# electronic_system.net
KiCad netlist of a schematic drawn in EAGLE
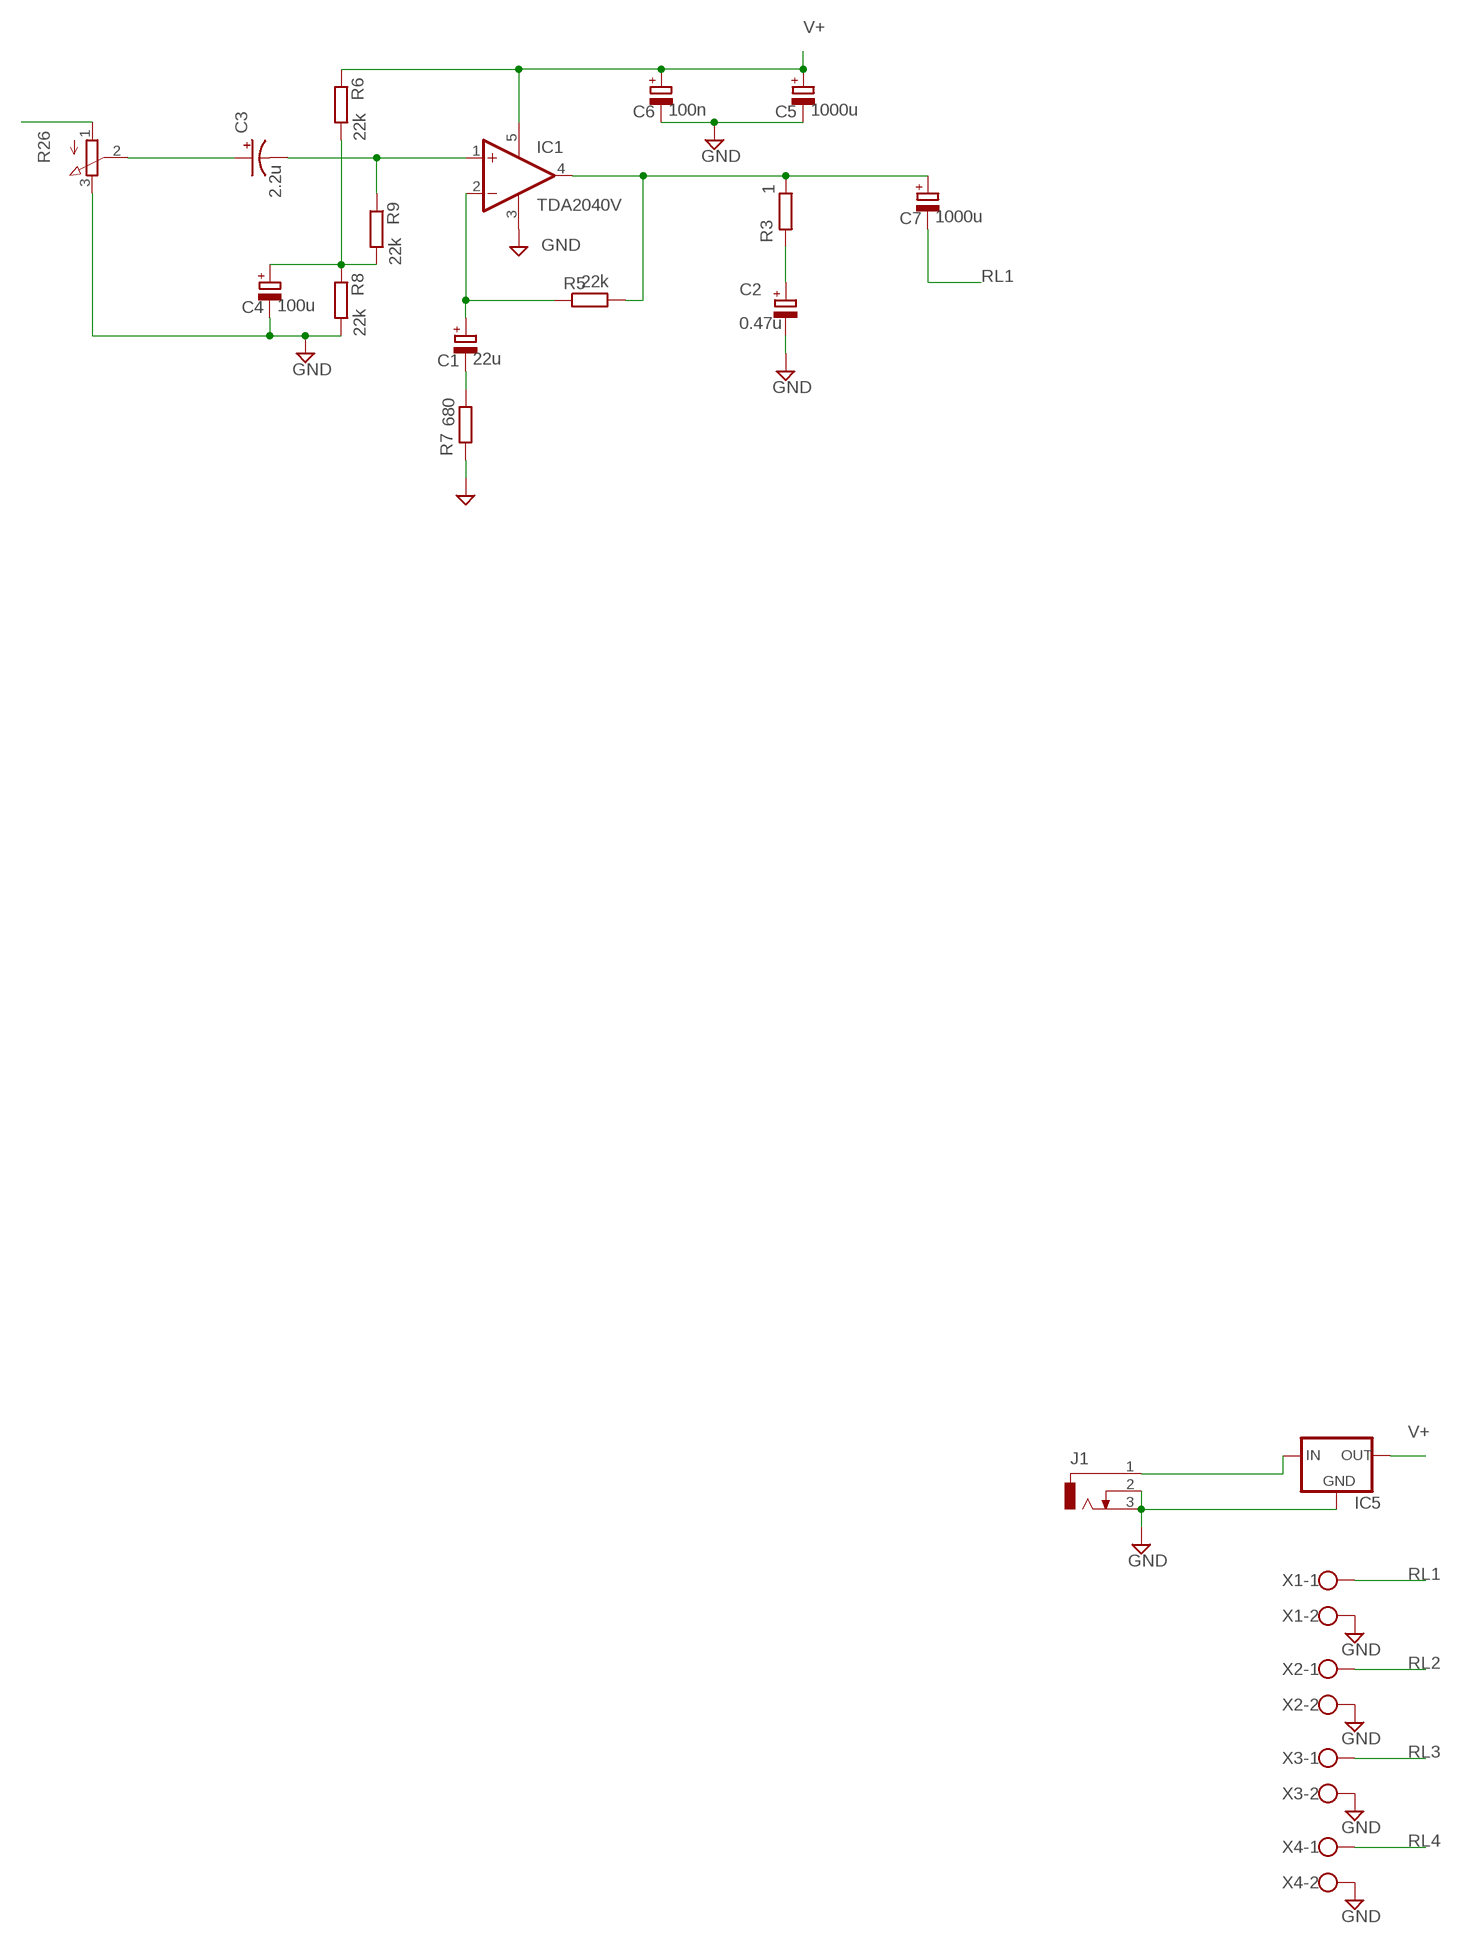
[diagram p0: schematic, sheet 1]

(export (version "E")
  (design (tool "Eeschema 10.0.6"))
  (components
    (comp (ref "C1")
      (value "22u")
      (footprint "eagle-import:E5-6")
      (libsource (lib "eagle-import") (part "CPOL-EUE5-6"))
    )
    (comp (ref "C2")
      (value "0.47u")
      (footprint "eagle-import:E5-5")
      (libsource (lib "eagle-import") (part "CPOL-EUE5-5"))
    )
    (comp (ref "C3")
      (value "2.2u")
      (footprint "eagle-import:TT5D11")
      (libsource (lib "eagle-import") (part "CPOL-USTT5D11"))
    )
    (comp (ref "C4")
      (value "100u")
      (footprint "eagle-import:E5-10,5")
      (libsource (lib "eagle-import") (part "CPOL-EUE5-10.5"))
    )
    (comp (ref "C5")
      (value "1000u")
      (footprint "eagle-import:E5-10,5")
      (libsource (lib "eagle-import") (part "CPOL-EUE5-10.5"))
    )
    (comp (ref "C6")
      (value "100n")
      (footprint "eagle-import:E5-5")
      (libsource (lib "eagle-import") (part "CPOL-EUE5-5"))
    )
    (comp (ref "C7")
      (value "1000u")
      (footprint "eagle-import:E5-10,5")
      (libsource (lib "eagle-import") (part "CPOL-EUE5-10.5"))
    )
    (comp (ref "IC1")
      (value "TDA2040V")
      (footprint "eagle-import:CB360")
      (libsource (lib "eagle-import") (part "TDA2040V"))
    )
    (comp (ref "IC5")
      (value "78XXS")
      (footprint "eagle-import:78XXS")
      (libsource (lib "eagle-import") (part "78XXS"))
    )
    (comp (ref "J1")
      (value "DCJ0303")
      (footprint "eagle-import:DCJ0303")
      (libsource (lib "eagle-import") (part "DCJ0303"))
    )
    (comp (ref "R3")
      (value "1")
      (footprint "eagle-import:0207_12")
      (libsource (lib "eagle-import") (part "R-EU_0207/12"))
    )
    (comp (ref "R5")
      (value "22k")
      (footprint "eagle-import:0207_12")
      (libsource (lib "eagle-import") (part "R-EU_0207/12"))
    )
    (comp (ref "R6")
      (value "22k")
      (footprint "eagle-import:0207_12")
      (libsource (lib "eagle-import") (part "R-EU_0207/12"))
    )
    (comp (ref "R7")
      (value "680")
      (footprint "eagle-import:0207_12")
      (libsource (lib "eagle-import") (part "R-EU_0207/12"))
    )
    (comp (ref "R8")
      (value "22k")
      (footprint "eagle-import:0207_12")
      (libsource (lib "eagle-import") (part "R-EU_0207/12"))
    )
    (comp (ref "R9")
      (value "22k")
      (footprint "eagle-import:0207_12")
      (libsource (lib "eagle-import") (part "R-EU_0207/12"))
    )
    (comp (ref "R26")
      (value "3RP/1610N")
      (footprint "eagle-import:3RP_1610N")
      (libsource (lib "eagle-import") (part "3RP/1610N"))
    )
    (comp (ref "X1")
      (value "W237-102")
      (footprint "eagle-import:W237-102")
      (fields (field (name "MPN") "237-102"))
      (libsource (lib "eagle-import") (part "W237-102"))
    )
    (comp (ref "X2")
      (value "W237-102")
      (footprint "eagle-import:W237-102")
      (fields (field (name "MPN") "237-102"))
      (libsource (lib "eagle-import") (part "W237-102"))
    )
    (comp (ref "X3")
      (value "W237-102")
      (footprint "eagle-import:W237-102")
      (fields (field (name "MPN") "237-102"))
      (libsource (lib "eagle-import") (part "W237-102"))
    )
    (comp (ref "X4")
      (value "W237-102")
      (footprint "eagle-import:W237-102")
      (fields (field (name "MPN") "237-102"))
      (libsource (lib "eagle-import") (part "W237-102"))
    )
  )
  (nets
    (net (code "1") (name "/RL1") (class "Default")
      (node (ref "C7") (pin "-") (pinfunction "-_-") (pintype "passive"))
      (node (ref "X1") (pin "1") (pinfunction "KL_1") (pintype "passive"))
    )
    (net (code "2") (name "/RL2") (class "Default")
      (node (ref "X2") (pin "1") (pinfunction "KL_1") (pintype "passive"))
    )
    (net (code "3") (name "/RL3") (class "Default")
      (node (ref "X3") (pin "1") (pinfunction "KL_1") (pintype "passive"))
    )
    (net (code "4") (name "/RL4") (class "Default")
      (node (ref "X4") (pin "1") (pinfunction "KL_1") (pintype "passive"))
    )
    (net (code "5") (name "/V+") (class "Default")
      (node (ref "C5") (pin "+") (pinfunction "+_+") (pintype "passive"))
      (node (ref "C6") (pin "+") (pinfunction "+_+") (pintype "passive"))
      (node (ref "IC1") (pin "5") (pinfunction "V+_5") (pintype "power_in"))
      (node (ref "IC5") (pin "OUT") (pinfunction "OUT_OUT") (pintype "passive"))
      (node (ref "R6") (pin "1") (pinfunction "1_1") (pintype "passive"))
    )
    (net (code "6") (name "GND") (class "Default")
      (node (ref "C2") (pin "-") (pinfunction "-_-") (pintype "passive"))
      (node (ref "C4") (pin "-") (pinfunction "-_-") (pintype "passive"))
      (node (ref "C5") (pin "-") (pinfunction "-_-") (pintype "passive"))
      (node (ref "C6") (pin "-") (pinfunction "-_-") (pintype "passive"))
      (node (ref "IC1") (pin "3") (pinfunction "V-_3") (pintype "power_in"))
      (node (ref "IC5") (pin "GND") (pinfunction "GND_GND") (pintype "input"))
      (node (ref "J1") (pin "2") (pinfunction "2_2") (pintype "passive"))
      (node (ref "J1") (pin "3") (pinfunction "3_3") (pintype "passive"))
      (node (ref "R26") (pin "3") (pinfunction "E_3") (pintype "passive"))
      (node (ref "R7") (pin "2") (pinfunction "2_2") (pintype "passive"))
      (node (ref "R8") (pin "2") (pinfunction "2_2") (pintype "passive"))
      (node (ref "X1") (pin "2") (pinfunction "KL_2") (pintype "passive"))
      (node (ref "X2") (pin "2") (pinfunction "KL_2") (pintype "passive"))
      (node (ref "X3") (pin "2") (pinfunction "KL_2") (pintype "passive"))
      (node (ref "X4") (pin "2") (pinfunction "KL_2") (pintype "passive"))
    )
    (net (code "7") (name "Net-(C1-Pad-)") (class "Default")
      (node (ref "C1") (pin "-") (pinfunction "-_-") (pintype "passive"))
      (node (ref "R7") (pin "1") (pinfunction "1_1") (pintype "passive"))
    )
    (net (code "8") (name "Net-(C2-Pad+)") (class "Default")
      (node (ref "C2") (pin "+") (pinfunction "+_+") (pintype "passive"))
      (node (ref "R3") (pin "2") (pinfunction "2_2") (pintype "passive"))
    )
    (net (code "9") (name "Net-(C4-Pad+)") (class "Default")
      (node (ref "C4") (pin "+") (pinfunction "+_+") (pintype "passive"))
      (node (ref "R6") (pin "2") (pinfunction "2_2") (pintype "passive"))
      (node (ref "R8") (pin "1") (pinfunction "1_1") (pintype "passive"))
      (node (ref "R9") (pin "2") (pinfunction "2_2") (pintype "passive"))
    )
    (net (code "10") (name "Net-(IC1-+IN)") (class "Default")
      (node (ref "C3") (pin "-") (pinfunction "-_-") (pintype "passive"))
      (node (ref "IC1") (pin "1") (pinfunction "+IN_1") (pintype "input"))
      (node (ref "R9") (pin "1") (pinfunction "1_1") (pintype "passive"))
    )
    (net (code "11") (name "Net-(IC1--IN)") (class "Default")
      (node (ref "C1") (pin "+") (pinfunction "+_+") (pintype "passive"))
      (node (ref "IC1") (pin "2") (pinfunction "-IN_2") (pintype "input"))
      (node (ref "R5") (pin "1") (pinfunction "1_1") (pintype "passive"))
    )
    (net (code "12") (name "Net-(IC1-OUT)") (class "Default")
      (node (ref "C7") (pin "+") (pinfunction "+_+") (pintype "passive"))
      (node (ref "IC1") (pin "4") (pinfunction "OUT_4") (pintype "output"))
      (node (ref "R3") (pin "1") (pinfunction "1_1") (pintype "passive"))
      (node (ref "R5") (pin "2") (pinfunction "2_2") (pintype "passive"))
    )
    (net (code "13") (name "Net-(IC5-PadIN)") (class "Default")
      (node (ref "IC5") (pin "IN") (pinfunction "IN_IN") (pintype "input"))
      (node (ref "J1") (pin "1") (pinfunction "1_1") (pintype "passive"))
    )
    (net (code "14") (name "Net-(R26-S)") (class "Default")
      (node (ref "C3") (pin "+") (pinfunction "+_+") (pintype "passive"))
      (node (ref "R26") (pin "2") (pinfunction "S_2") (pintype "passive"))
    )
    (net (code "15") (name "unconnected-(R26-A-Pad1)") (class "Default")
      (node (ref "R26") (pin "1") (pinfunction "A_1") (pintype "passive"))
    )
  )
)
